# BeerCannon.net
KiCad netlist of a schematic drawn in EAGLE
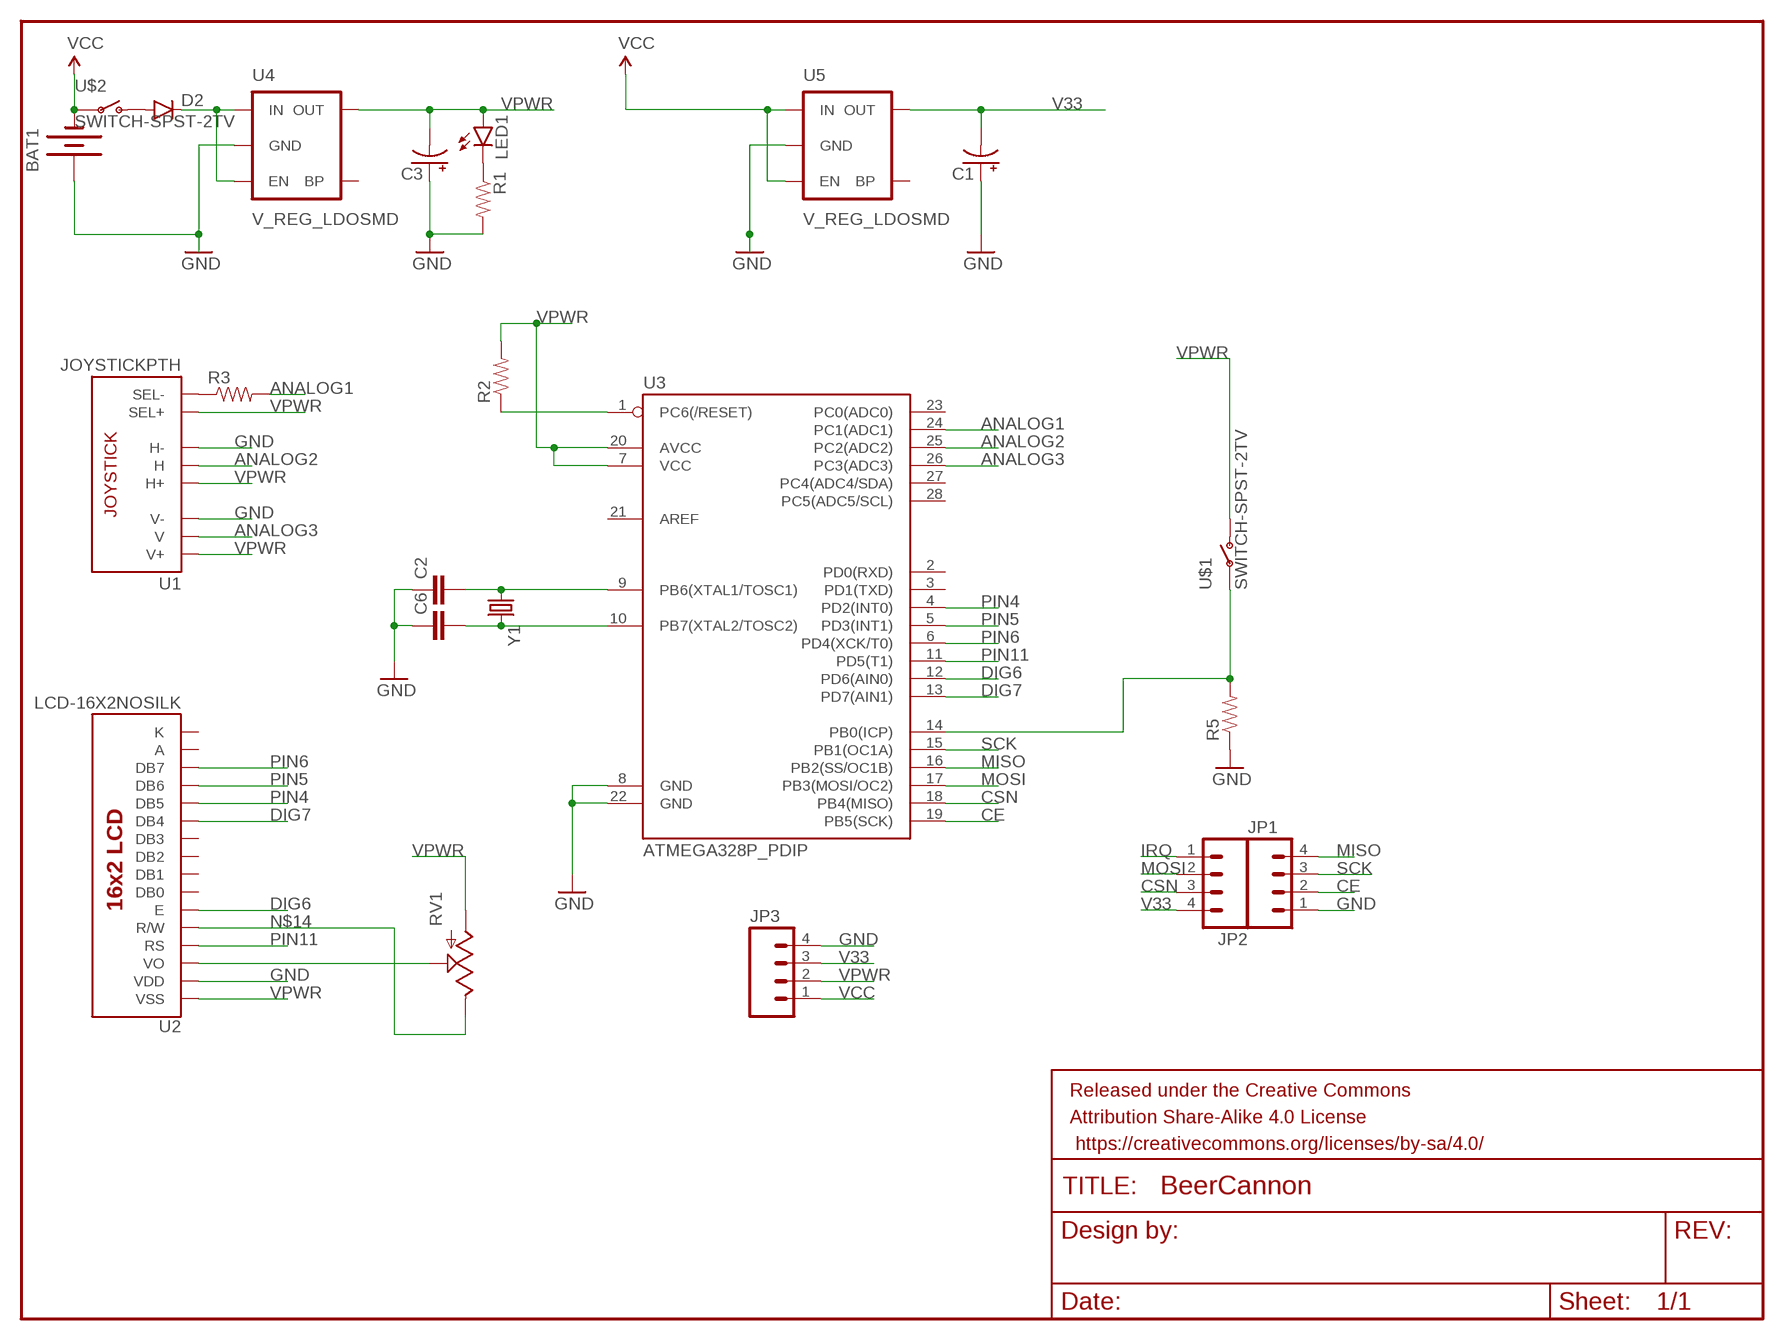
[diagram p0: schematic, sheet 1]

(export (version "E")
  (design (tool "Eeschema 10.0.6"))
  (components
    (comp (ref "BAT1")
      (value "BATTERY9V")
      (footprint "eagle-import:BATTCON_9V")
      (libsource (lib "eagle-import") (part "BATTERY9V"))
    )
    (comp (ref "C1")
      (value "CAP_POL1206")
      (footprint "eagle-import:EIA3216")
      (libsource (lib "eagle-import") (part "CAP_POL1206"))
    )
    (comp (ref "C2")
      (value "CAP1206")
      (footprint "eagle-import:1206")
      (libsource (lib "eagle-import") (part "CAP1206"))
    )
    (comp (ref "C3")
      (value "CAP_POL1206")
      (footprint "eagle-import:EIA3216")
      (libsource (lib "eagle-import") (part "CAP_POL1206"))
    )
    (comp (ref "C6")
      (value "CAP1206")
      (footprint "eagle-import:1206")
      (libsource (lib "eagle-import") (part "CAP1206"))
    )
    (comp (ref "D2")
      (value "DIODESMA")
      (footprint "eagle-import:SMA-DIODE")
      (libsource (lib "eagle-import") (part "DIODESMA"))
    )
    (comp (ref "FRAME1")
      (value "FRAME-LETTER")
      (footprint "eagle-import:CREATIVE_COMMONS")
      (libsource (lib "eagle-import") (part "FRAME-LETTER"))
    )
    (comp (ref "JP1")
      (value "M04PTH")
      (footprint "eagle-import:1X04")
      (libsource (lib "eagle-import") (part "M04PTH"))
    )
    (comp (ref "JP2")
      (value "M04PTH")
      (footprint "eagle-import:1X04")
      (libsource (lib "eagle-import") (part "M04PTH"))
    )
    (comp (ref "JP3")
      (value "M04PTH")
      (footprint "eagle-import:1X04")
      (libsource (lib "eagle-import") (part "M04PTH"))
    )
    (comp (ref "LED1")
      (value "LED1206")
      (footprint "eagle-import:LED-1206")
      (libsource (lib "eagle-import") (part "LED1206"))
    )
    (comp (ref "R1")
      (value "RESISTOR1206")
      (footprint "eagle-import:1206")
      (libsource (lib "eagle-import") (part "RESISTOR1206"))
    )
    (comp (ref "R2")
      (value "RESISTOR1206")
      (footprint "eagle-import:1206")
      (libsource (lib "eagle-import") (part "RESISTOR1206"))
    )
    (comp (ref "R3")
      (value "RESISTOR1206")
      (footprint "eagle-import:1206")
      (libsource (lib "eagle-import") (part "RESISTOR1206"))
    )
    (comp (ref "R5")
      (value "RESISTOR1206")
      (footprint "eagle-import:1206")
      (libsource (lib "eagle-import") (part "RESISTOR1206"))
    )
    (comp (ref "RV1")
      (value "POT")
      (footprint "eagle-import:ALPS_POT")
      (libsource (lib "eagle-import") (part "POT"))
    )
    (comp (ref "U$1")
      (value "SWITCH-SPST-2TV")
      (footprint "eagle-import:SWITCH-SPST-VERTICAL")
      (libsource (lib "eagle-import") (part "SWITCH-SPST-2TV"))
    )
    (comp (ref "U$2")
      (value "SWITCH-SPST-2TV")
      (footprint "eagle-import:SWITCH-SPST-VERTICAL")
      (libsource (lib "eagle-import") (part "SWITCH-SPST-2TV"))
    )
    (comp (ref "U1")
      (value "JOYSTICKPTH")
      (footprint "eagle-import:JOYSTICK")
      (libsource (lib "eagle-import") (part "JOYSTICKPTH"))
    )
    (comp (ref "U2")
      (value "LCD-16X2NOSILK")
      (footprint "eagle-import:LCD-16X2_NOSILK")
      (libsource (lib "eagle-import") (part "LCD-16X2NOSILK"))
    )
    (comp (ref "U3")
      (value "ATMEGA328P_PDIP")
      (footprint "eagle-import:DIL28-3")
      (libsource (lib "eagle-import") (part "ATMEGA328P_PDIP"))
    )
    (comp (ref "U4")
      (value "V_REG_LDOSMD")
      (footprint "eagle-import:SOT23-5")
      (libsource (lib "eagle-import") (part "V_REG_LDOSMD"))
    )
    (comp (ref "U5")
      (value "V_REG_LDOSMD")
      (footprint "eagle-import:SOT23-5")
      (libsource (lib "eagle-import") (part "V_REG_LDOSMD"))
    )
    (comp (ref "Y1")
      (value "CRYSTALSMD")
      (footprint "eagle-import:HC49UP")
      (libsource (lib "eagle-import") (part "CRYSTALSMD"))
    )
  )
  (nets
    (net (code "1") (name "/A") (class "Default")
      (node (ref "U2") (pin "15") (pinfunction "A_15") (pintype "power_in"))
    )
    (net (code "2") (name "/ANALOG1") (class "Default")
      (node (ref "R3") (pin "2") (pinfunction "2_2") (pintype "passive"))
      (node (ref "U3") (pin "24") (pinfunction "PC1(ADC1)_24") (pintype "bidirectional"))
    )
    (net (code "3") (name "/ANALOG2") (class "Default")
      (node (ref "U1") (pin "H2") (pinfunction "H_H2") (pintype "bidirectional"))
      (node (ref "U3") (pin "25") (pinfunction "PC2(ADC2)_25") (pintype "bidirectional"))
    )
    (net (code "4") (name "/ANALOG3") (class "Default")
      (node (ref "U1") (pin "V2") (pinfunction "V_V2") (pintype "bidirectional"))
      (node (ref "U3") (pin "26") (pinfunction "PC3(ADC3)_26") (pintype "bidirectional"))
    )
    (net (code "5") (name "/CE") (class "Default")
      (node (ref "JP1") (pin "2") (pinfunction "2_2") (pintype "passive"))
      (node (ref "U3") (pin "19") (pinfunction "PB5(SCK)_19") (pintype "bidirectional"))
    )
    (net (code "6") (name "/CSN") (class "Default")
      (node (ref "JP2") (pin "3") (pinfunction "3_3") (pintype "passive"))
      (node (ref "U3") (pin "18") (pinfunction "PB4(MISO)_18") (pintype "bidirectional"))
    )
    (net (code "7") (name "/DIG6") (class "Default")
      (node (ref "U2") (pin "6") (pinfunction "E_6") (pintype "input"))
      (node (ref "U3") (pin "12") (pinfunction "PD6(AIN0)_12") (pintype "bidirectional"))
    )
    (net (code "8") (name "/DIG7") (class "Default")
      (node (ref "U2") (pin "11") (pinfunction "DB4_11") (pintype "bidirectional"))
      (node (ref "U3") (pin "13") (pinfunction "PD7(AIN1)_13") (pintype "bidirectional"))
    )
    (net (code "9") (name "/IRQ") (class "Default")
      (node (ref "JP2") (pin "1") (pinfunction "1_1") (pintype "passive"))
    )
    (net (code "10") (name "/K") (class "Default")
      (node (ref "U2") (pin "16") (pinfunction "K_16") (pintype "power_in"))
    )
    (net (code "11") (name "/MISO") (class "Default")
      (node (ref "JP1") (pin "4") (pinfunction "4_4") (pintype "passive"))
      (node (ref "U3") (pin "16") (pinfunction "PB2(SS/OC1B)_16") (pintype "bidirectional"))
    )
    (net (code "12") (name "/MOSI") (class "Default")
      (node (ref "JP2") (pin "2") (pinfunction "2_2") (pintype "passive"))
      (node (ref "U3") (pin "17") (pinfunction "PB3(MOSI/OC2)_17") (pintype "bidirectional"))
    )
    (net (code "13") (name "/N$14") (class "Default")
      (node (ref "RV1") (pin "P$1") (pinfunction "E_P$1") (pintype "passive"))
      (node (ref "U2") (pin "5") (pinfunction "R/W_5") (pintype "input"))
    )
    (net (code "14") (name "/PIN4") (class "Default")
      (node (ref "U2") (pin "12") (pinfunction "DB5_12") (pintype "bidirectional"))
      (node (ref "U3") (pin "4") (pinfunction "PD2(INT0)_4") (pintype "bidirectional"))
    )
    (net (code "15") (name "/PIN5") (class "Default")
      (node (ref "U2") (pin "13") (pinfunction "DB6_13") (pintype "bidirectional"))
      (node (ref "U3") (pin "5") (pinfunction "PD3(INT1)_5") (pintype "bidirectional"))
    )
    (net (code "16") (name "/PIN6") (class "Default")
      (node (ref "U2") (pin "14") (pinfunction "DB7_14") (pintype "bidirectional"))
      (node (ref "U3") (pin "6") (pinfunction "PD4(XCK/T0)_6") (pintype "bidirectional"))
    )
    (net (code "17") (name "/PIN11") (class "Default")
      (node (ref "U2") (pin "4") (pinfunction "RS_4") (pintype "input"))
      (node (ref "U3") (pin "11") (pinfunction "PD5(T1)_11") (pintype "bidirectional"))
    )
    (net (code "18") (name "/SCK") (class "Default")
      (node (ref "JP1") (pin "3") (pinfunction "3_3") (pintype "passive"))
      (node (ref "U3") (pin "15") (pinfunction "PB1(OC1A)_15") (pintype "bidirectional"))
    )
    (net (code "19") (name "/V33") (class "Default")
      (node (ref "C1") (pin "C") (pinfunction "-_C") (pintype "passive"))
      (node (ref "JP2") (pin "4") (pinfunction "4_4") (pintype "passive"))
      (node (ref "JP3") (pin "3") (pinfunction "3_3") (pintype "passive"))
      (node (ref "U5") (pin "5") (pinfunction "OUT_5") (pintype "passive"))
    )
    (net (code "20") (name "/VPWR") (class "Default")
      (node (ref "C3") (pin "C") (pinfunction "-_C") (pintype "passive"))
      (node (ref "JP3") (pin "2") (pinfunction "2_2") (pintype "passive"))
      (node (ref "LED1") (pin "A") (pinfunction "A_A") (pintype "passive"))
      (node (ref "R2") (pin "2") (pinfunction "2_2") (pintype "passive"))
      (node (ref "RV1") (pin "P$3") (pinfunction "A_P$3") (pintype "passive"))
      (node (ref "U$1") (pin "1") (pinfunction "O_1") (pintype "passive"))
      (node (ref "U1") (pin "B1A") (pinfunction "SEL+_B1A") (pintype "bidirectional"))
      (node (ref "U1") (pin "H1") (pinfunction "H+_H1") (pintype "bidirectional"))
      (node (ref "U1") (pin "V1") (pinfunction "V+_V1") (pintype "bidirectional"))
      (node (ref "U2") (pin "1") (pinfunction "VSS_1") (pintype "power_in"))
      (node (ref "U3") (pin "20") (pinfunction "AVCC_20") (pintype "bidirectional"))
      (node (ref "U3") (pin "7") (pinfunction "VCC_7") (pintype "bidirectional"))
      (node (ref "U4") (pin "5") (pinfunction "OUT_5") (pintype "passive"))
    )
    (net (code "21") (name "GND") (class "Default")
      (node (ref "BAT1") (pin "+") (pinfunction "+_+") (pintype "power_in"))
      (node (ref "C1") (pin "A") (pinfunction "+_A") (pintype "passive"))
      (node (ref "C2") (pin "1") (pinfunction "1_1") (pintype "passive"))
      (node (ref "C3") (pin "A") (pinfunction "+_A") (pintype "passive"))
      (node (ref "C6") (pin "1") (pinfunction "1_1") (pintype "passive"))
      (node (ref "JP1") (pin "1") (pinfunction "1_1") (pintype "passive"))
      (node (ref "JP3") (pin "4") (pinfunction "4_4") (pintype "passive"))
      (node (ref "R1") (pin "2") (pinfunction "2_2") (pintype "passive"))
      (node (ref "R5") (pin "1") (pinfunction "1_1") (pintype "passive"))
      (node (ref "U1") (pin "H3") (pinfunction "H-_H3") (pintype "bidirectional"))
      (node (ref "U1") (pin "V3") (pinfunction "V-_V3") (pintype "bidirectional"))
      (node (ref "U2") (pin "2") (pinfunction "VDD_2") (pintype "power_in"))
      (node (ref "U3") (pin "22") (pinfunction "GND_22") (pintype "bidirectional"))
      (node (ref "U3") (pin "8") (pinfunction "GND_8") (pintype "bidirectional"))
      (node (ref "U4") (pin "2") (pinfunction "GND_2") (pintype "input"))
      (node (ref "U5") (pin "2") (pinfunction "GND_2") (pintype "input"))
    )
    (net (code "22") (name "Net-(LED1-PadC)") (class "Default")
      (node (ref "LED1") (pin "C") (pinfunction "C_C") (pintype "passive"))
      (node (ref "R1") (pin "1") (pinfunction "1_1") (pintype "passive"))
    )
    (net (code "23") (name "Net-(RV1-S)") (class "Default")
      (node (ref "RV1") (pin "P$2") (pinfunction "S_P$2") (pintype "passive"))
      (node (ref "U2") (pin "3") (pinfunction "VO_3") (pintype "bidirectional"))
    )
    (net (code "24") (name "Net-(U$1-P)") (class "Default")
      (node (ref "R5") (pin "2") (pinfunction "2_2") (pintype "passive"))
      (node (ref "U$1") (pin "2") (pinfunction "P_2") (pintype "passive"))
      (node (ref "U3") (pin "14") (pinfunction "PB0(ICP)_14") (pintype "bidirectional"))
    )
    (net (code "25") (name "Net-(U$2-O)") (class "Default")
      (node (ref "D2") (pin "A") (pinfunction "A_A") (pintype "passive"))
      (node (ref "U$2") (pin "1") (pinfunction "O_1") (pintype "passive"))
    )
    (net (code "26") (name "Net-(U1-SEL-)") (class "Default")
      (node (ref "R3") (pin "1") (pinfunction "1_1") (pintype "passive"))
      (node (ref "U1") (pin "B2A") (pinfunction "SEL-_B2A") (pintype "bidirectional"))
    )
    (net (code "27") (name "Net-(U3-PB6(XTAL1{slash}TOSC1))") (class "Default")
      (node (ref "C2") (pin "2") (pinfunction "2_2") (pintype "passive"))
      (node (ref "U3") (pin "9") (pinfunction "PB6(XTAL1/TOSC1)_9") (pintype "bidirectional"))
      (node (ref "Y1") (pin "1") (pinfunction "1_1") (pintype "passive"))
    )
    (net (code "28") (name "Net-(U3-PB7(XTAL2{slash}TOSC2))") (class "Default")
      (node (ref "C6") (pin "2") (pinfunction "2_2") (pintype "passive"))
      (node (ref "U3") (pin "10") (pinfunction "PB7(XTAL2/TOSC2)_10") (pintype "bidirectional"))
      (node (ref "Y1") (pin "2") (pinfunction "2_2") (pintype "passive"))
    )
    (net (code "29") (name "Net-(U3-PC6({slash}RESET))") (class "Default")
      (node (ref "R2") (pin "1") (pinfunction "1_1") (pintype "passive"))
      (node (ref "U3") (pin "1") (pinfunction "PC6(/RESET)_1") (pintype "bidirectional"))
    )
    (net (code "30") (name "Net-(U4-EN)") (class "Default")
      (node (ref "D2") (pin "C") (pinfunction "C_C") (pintype "passive"))
      (node (ref "U4") (pin "1") (pinfunction "IN_1") (pintype "input"))
      (node (ref "U4") (pin "3") (pinfunction "EN_3") (pintype "input"))
    )
    (net (code "31") (name "VCC") (class "Default")
      (node (ref "BAT1") (pin "-") (pinfunction "-_-") (pintype "power_in"))
      (node (ref "JP3") (pin "1") (pinfunction "1_1") (pintype "passive"))
      (node (ref "U$2") (pin "2") (pinfunction "P_2") (pintype "passive"))
      (node (ref "U5") (pin "1") (pinfunction "IN_1") (pintype "input"))
      (node (ref "U5") (pin "3") (pinfunction "EN_3") (pintype "input"))
    )
    (net (code "32") (name "unconnected-(U2-DB0-Pad7)") (class "Default")
      (node (ref "U2") (pin "7") (pinfunction "DB0_7") (pintype "bidirectional"))
    )
    (net (code "33") (name "unconnected-(U2-DB1-Pad8)") (class "Default")
      (node (ref "U2") (pin "8") (pinfunction "DB1_8") (pintype "bidirectional"))
    )
    (net (code "34") (name "unconnected-(U2-DB2-Pad9)") (class "Default")
      (node (ref "U2") (pin "9") (pinfunction "DB2_9") (pintype "bidirectional"))
    )
    (net (code "35") (name "unconnected-(U2-DB3-Pad10)") (class "Default")
      (node (ref "U2") (pin "10") (pinfunction "DB3_10") (pintype "bidirectional"))
    )
    (net (code "36") (name "unconnected-(U3-AREF-Pad21)") (class "Default")
      (node (ref "U3") (pin "21") (pinfunction "AREF_21") (pintype "bidirectional"))
    )
    (net (code "37") (name "unconnected-(U3-PC0(ADC0)-Pad23)") (class "Default")
      (node (ref "U3") (pin "23") (pinfunction "PC0(ADC0)_23") (pintype "bidirectional"))
    )
    (net (code "38") (name "unconnected-(U3-PC4(ADC4{slash}SDA)-Pad27)") (class "Default")
      (node (ref "U3") (pin "27") (pinfunction "PC4(ADC4/SDA)_27") (pintype "bidirectional"))
    )
    (net (code "39") (name "unconnected-(U3-PC5(ADC5{slash}SCL)-Pad28)") (class "Default")
      (node (ref "U3") (pin "28") (pinfunction "PC5(ADC5/SCL)_28") (pintype "bidirectional"))
    )
    (net (code "40") (name "unconnected-(U3-PD0(RXD)-Pad2)") (class "Default")
      (node (ref "U3") (pin "2") (pinfunction "PD0(RXD)_2") (pintype "bidirectional"))
    )
    (net (code "41") (name "unconnected-(U3-PD1(TXD)-Pad3)") (class "Default")
      (node (ref "U3") (pin "3") (pinfunction "PD1(TXD)_3") (pintype "bidirectional"))
    )
    (net (code "42") (name "unconnected-(U4-BP-Pad4)") (class "Default")
      (node (ref "U4") (pin "4") (pinfunction "BP_4") (pintype "input"))
    )
    (net (code "43") (name "unconnected-(U5-BP-Pad4)") (class "Default")
      (node (ref "U5") (pin "4") (pinfunction "BP_4") (pintype "input"))
    )
  )
)
